# design.net
KiCad netlist of a schematic drawn in Altium Designer
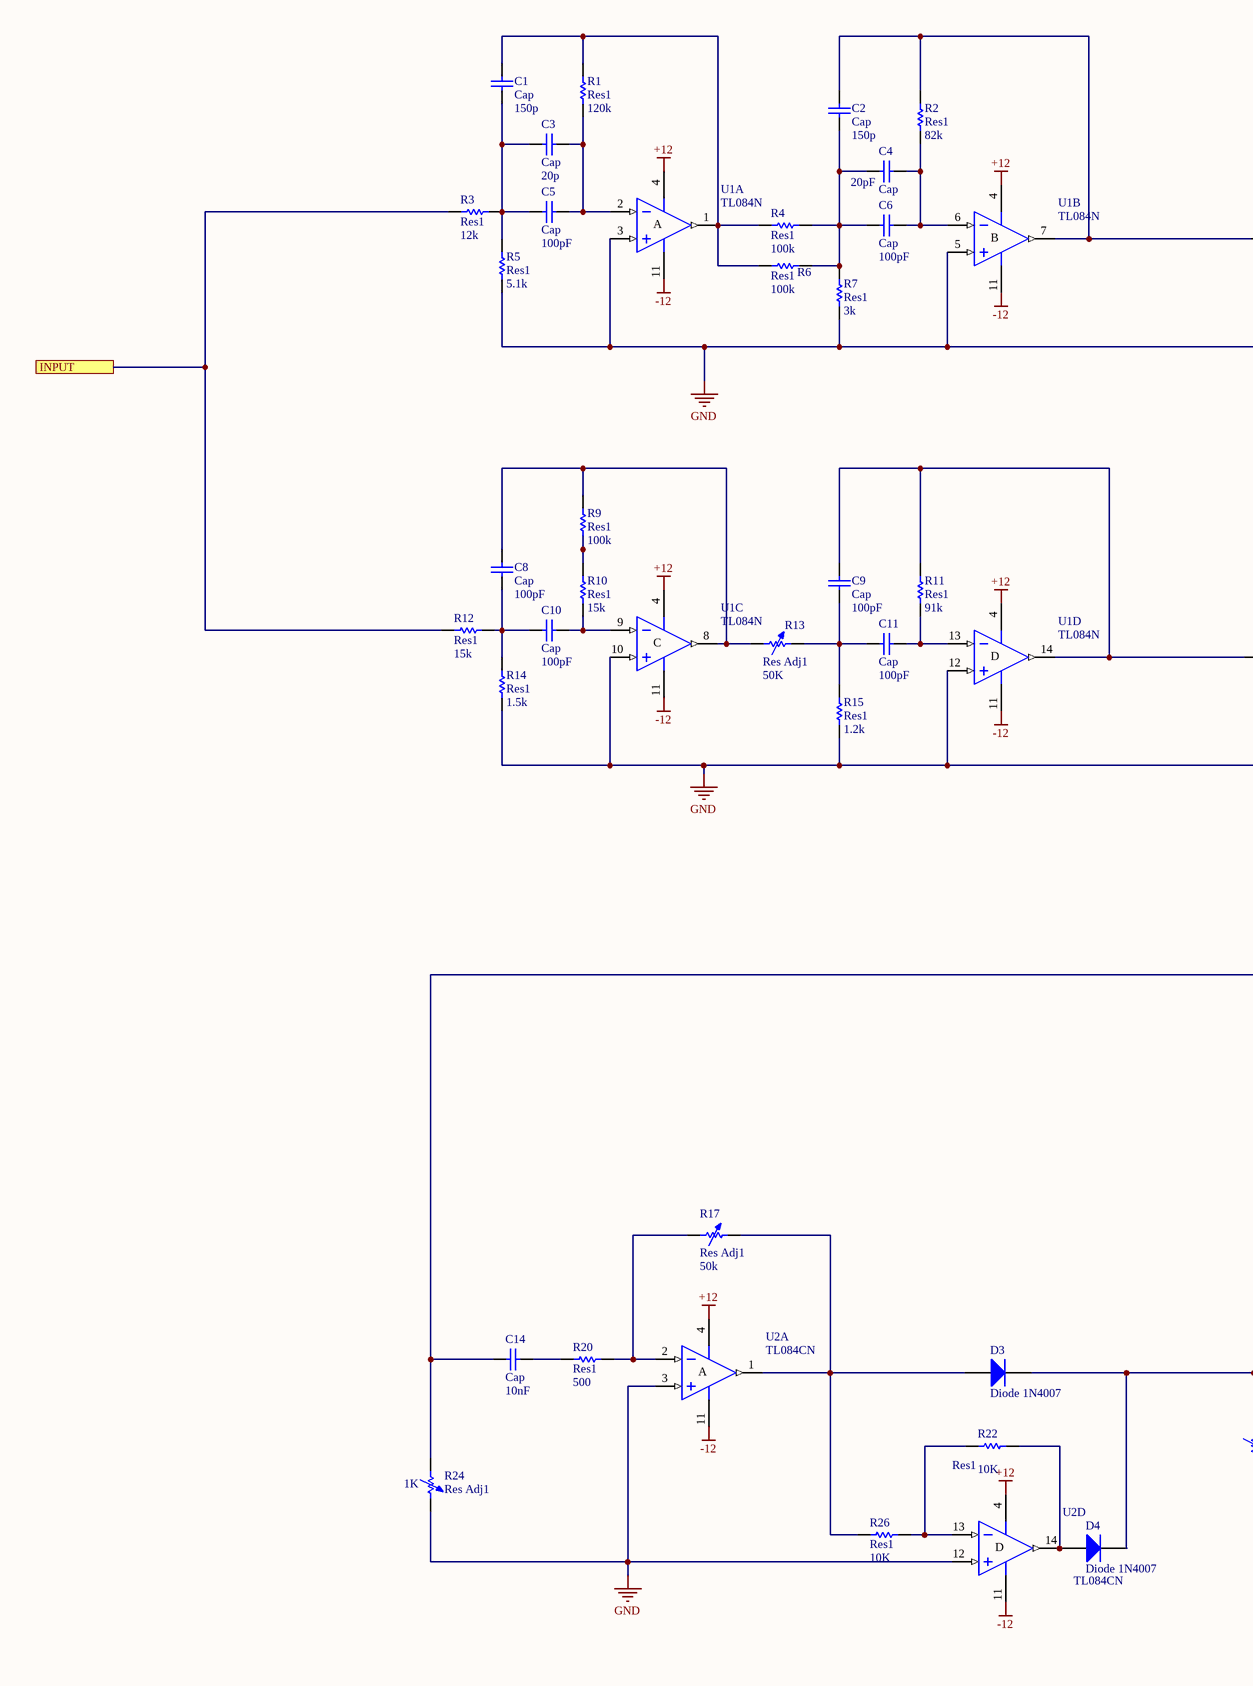
[diagram p0: 解调板原理图.SchDoc, left]
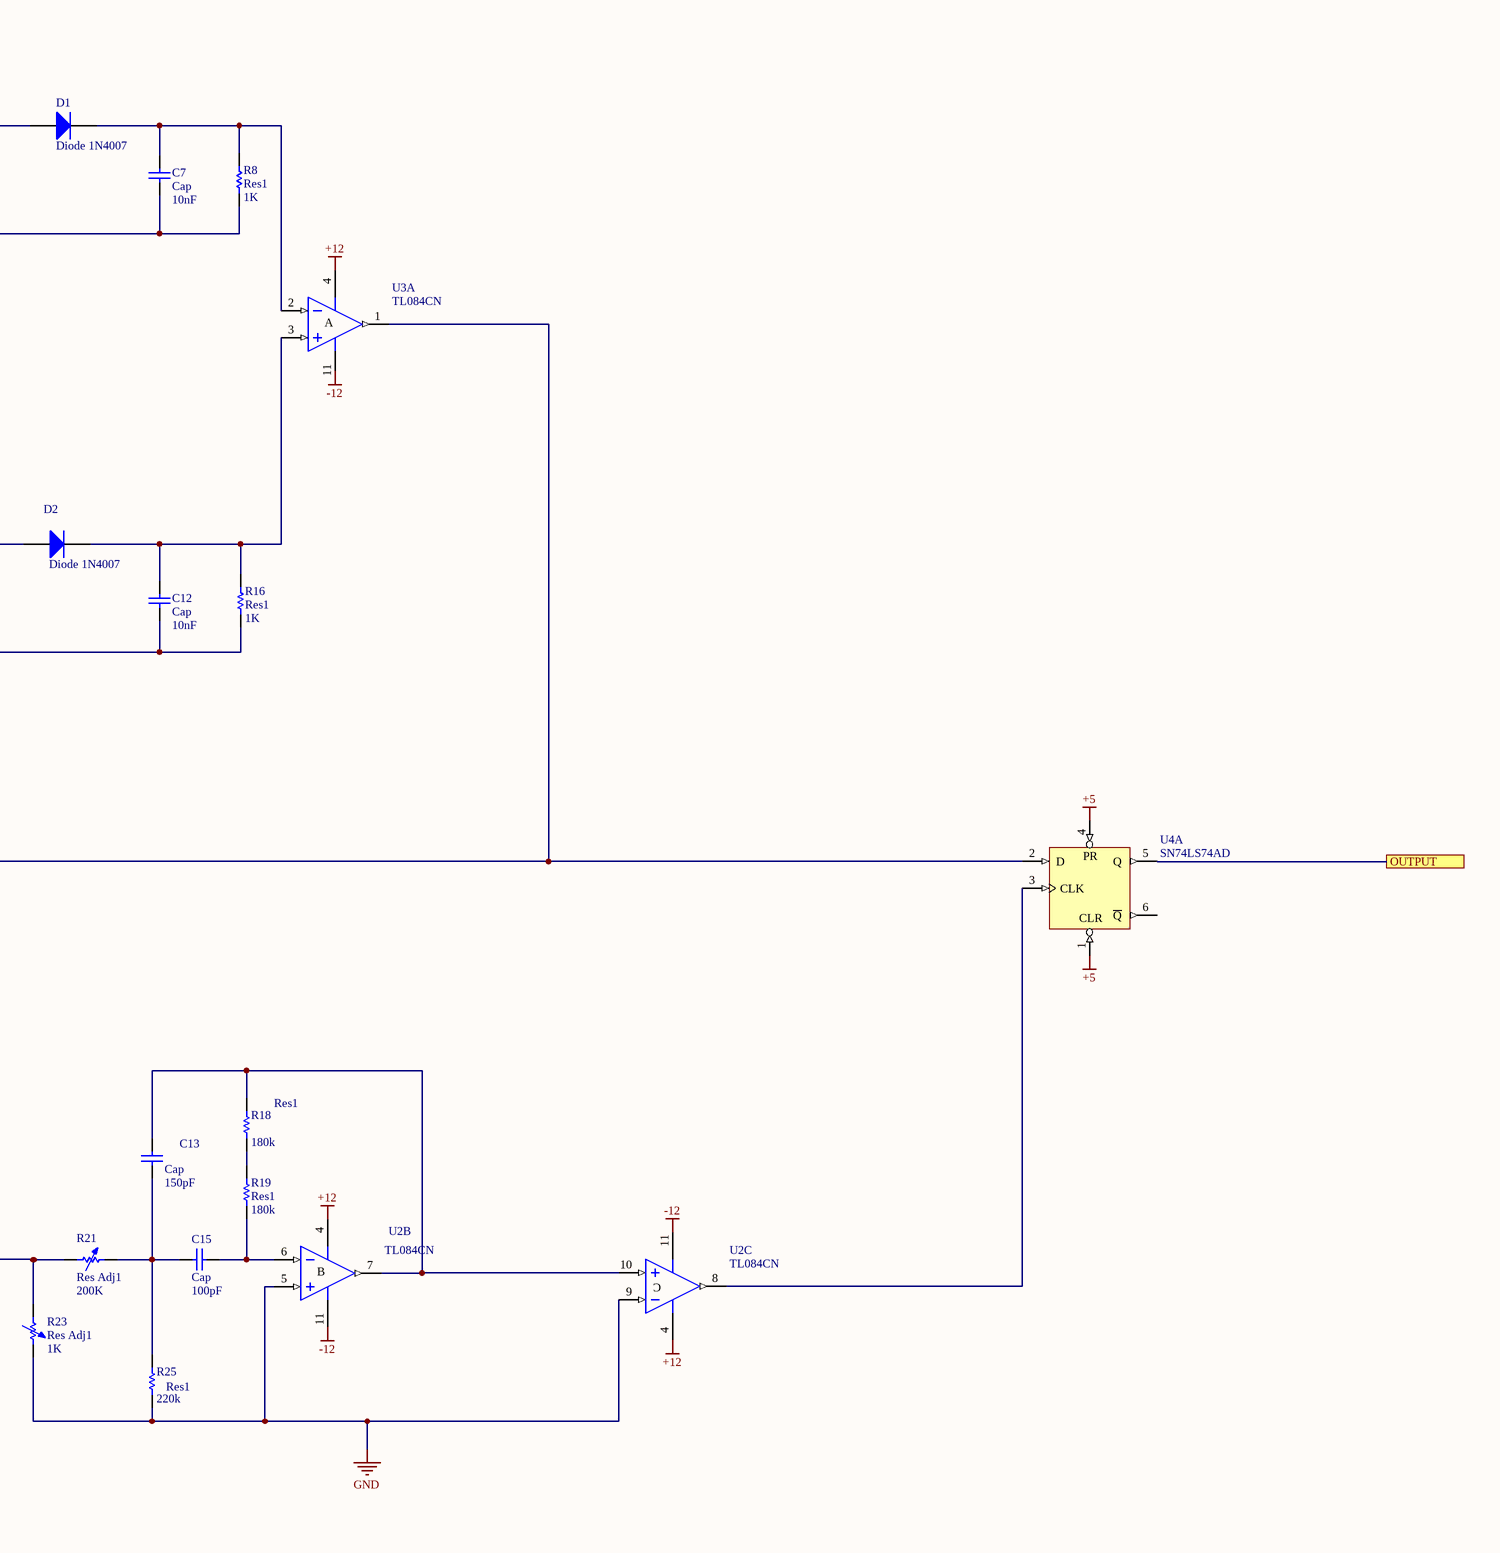
[diagram p1: 解调板原理图.SchDoc, right]

(export (version "E")
  (design (tool "Eeschema 10.0.6"))
  (components
    (comp (ref "C1")
      (value "Cap")
      (footprint "RAD-0.3")
      (description "Capacitor")
      (fields (field (name "ALTIUM_VALUE") "150p") (field (name "PUBLISHER") "Altium Limited"))
      (libsource (lib "Miscellaneous Devices") (part "Cap"))
    )
    (comp (ref "C2")
      (value "Cap")
      (footprint "RAD-0.3")
      (description "Capacitor")
      (fields (field (name "ALTIUM_VALUE") "150p") (field (name "PUBLISHER") "Altium Limited"))
      (libsource (lib "Miscellaneous Devices") (part "Cap"))
    )
    (comp (ref "C3")
      (value "Cap")
      (footprint "RAD-0.3")
      (description "Capacitor")
      (fields (field (name "ALTIUM_VALUE") "20p") (field (name "PUBLISHER") "Altium Limited"))
      (libsource (lib "Miscellaneous Devices") (part "Cap"))
    )
    (comp (ref "C4")
      (value "Cap")
      (footprint "RAD-0.3")
      (description "Capacitor")
      (fields (field (name "ALTIUM_VALUE") "20pF") (field (name "PUBLISHER") "Altium Limited"))
      (libsource (lib "Miscellaneous Devices") (part "Cap"))
    )
    (comp (ref "C5")
      (value "Cap")
      (footprint "RAD-0.3")
      (description "Capacitor")
      (fields (field (name "ALTIUM_VALUE") "100pF") (field (name "PUBLISHER") "Altium Limited"))
      (libsource (lib "Miscellaneous Devices") (part "Cap"))
    )
    (comp (ref "C6")
      (value "Cap")
      (footprint "RAD-0.3")
      (description "Capacitor")
      (fields (field (name "ALTIUM_VALUE") "100pF") (field (name "PUBLISHER") "Altium Limited"))
      (libsource (lib "Miscellaneous Devices") (part "Cap"))
    )
    (comp (ref "C7")
      (value "Cap")
      (footprint "RAD-0.3")
      (description "Capacitor")
      (fields (field (name "ALTIUM_VALUE") "10nF") (field (name "PUBLISHER") "Altium Limited"))
      (libsource (lib "Miscellaneous Devices") (part "Cap"))
    )
    (comp (ref "C8")
      (value "Cap")
      (footprint "RAD-0.3")
      (description "Capacitor")
      (fields (field (name "ALTIUM_VALUE") "100pF") (field (name "PUBLISHER") "Altium Limited"))
      (libsource (lib "Miscellaneous Devices") (part "Cap"))
    )
    (comp (ref "C9")
      (value "Cap")
      (footprint "RAD-0.3")
      (description "Capacitor")
      (fields (field (name "ALTIUM_VALUE") "100pF") (field (name "PUBLISHER") "Altium Limited"))
      (libsource (lib "Miscellaneous Devices") (part "Cap"))
    )
    (comp (ref "C10")
      (value "Cap")
      (footprint "RAD-0.3")
      (description "Capacitor")
      (fields (field (name "ALTIUM_VALUE") "100pF") (field (name "PUBLISHER") "Altium Limited"))
      (libsource (lib "Miscellaneous Devices") (part "Cap"))
    )
    (comp (ref "C11")
      (value "Cap")
      (footprint "RAD-0.3")
      (description "Capacitor")
      (fields (field (name "ALTIUM_VALUE") "100pF") (field (name "PUBLISHER") "Altium Limited"))
      (libsource (lib "Miscellaneous Devices") (part "Cap"))
    )
    (comp (ref "C12")
      (value "Cap")
      (footprint "RAD-0.3")
      (description "Capacitor")
      (fields (field (name "ALTIUM_VALUE") "10nF") (field (name "PUBLISHER") "Altium Limited"))
      (libsource (lib "Miscellaneous Devices") (part "Cap"))
    )
    (comp (ref "C13")
      (value "Cap")
      (footprint "RAD-0.3")
      (description "Capacitor")
      (fields (field (name "ALTIUM_VALUE") "150pF") (field (name "PUBLISHER") "Altium Limited"))
      (libsource (lib "Miscellaneous Devices") (part "Cap"))
    )
    (comp (ref "C14")
      (value "Cap")
      (footprint "RAD-0.3")
      (description "Capacitor")
      (fields (field (name "ALTIUM_VALUE") "10nF") (field (name "PUBLISHER") "Altium Limited"))
      (libsource (lib "Miscellaneous Devices") (part "Cap"))
    )
    (comp (ref "C15")
      (value "Cap")
      (footprint "RAD-0.3")
      (description "Capacitor")
      (fields (field (name "ALTIUM_VALUE") "100pF") (field (name "PUBLISHER") "Altium Limited"))
      (libsource (lib "Miscellaneous Devices") (part "Cap"))
    )
    (comp (ref "D1")
      (value "Diode 1N4007")
      (footprint "DO-41")
      (description "1 Amp General Purpose Rectifier")
      (fields (field (name "PUBLISHER") "Altium Limited"))
      (libsource (lib "Miscellaneous Devices") (part "Diode 1N4001"))
    )
    (comp (ref "D2")
      (value "Diode 1N4007")
      (footprint "DO-41")
      (description "1 Amp General Purpose Rectifier")
      (fields (field (name "PUBLISHER") "Altium Limited"))
      (libsource (lib "Miscellaneous Devices") (part "Diode 1N4001"))
    )
    (comp (ref "D3")
      (value "Diode 1N4007")
      (footprint "DO-41")
      (description "1 Amp General Purpose Rectifier")
      (fields (field (name "PUBLISHER") "Altium Limited"))
      (libsource (lib "Miscellaneous Devices") (part "Diode 1N4001"))
    )
    (comp (ref "D4")
      (value "Diode 1N4007")
      (footprint "DO-41")
      (description "1 Amp General Purpose Rectifier")
      (fields (field (name "PUBLISHER") "Altium Limited"))
      (libsource (lib "Miscellaneous Devices") (part "Diode 1N4001"))
    )
    (comp (ref "R1")
      (value "Res1")
      (footprint "AXIAL-0.3")
      (description "Resistor")
      (fields (field (name "ALTIUM_VALUE") "120k") (field (name "PUBLISHER") "Altium Limited"))
      (libsource (lib "Miscellaneous Devices") (part "Res1"))
    )
    (comp (ref "R2")
      (value "Res1")
      (footprint "AXIAL-0.3")
      (description "Resistor")
      (fields (field (name "ALTIUM_VALUE") "82k") (field (name "PUBLISHER") "Altium Limited"))
      (libsource (lib "Miscellaneous Devices") (part "Res1"))
    )
    (comp (ref "R3")
      (value "Res1")
      (footprint "AXIAL-0.3")
      (description "Resistor")
      (fields (field (name "ALTIUM_VALUE") "12k") (field (name "PUBLISHER") "Altium Limited"))
      (libsource (lib "Miscellaneous Devices") (part "Res1"))
    )
    (comp (ref "R4")
      (value "Res1")
      (footprint "AXIAL-0.3")
      (description "Resistor")
      (fields (field (name "ALTIUM_VALUE") "100k") (field (name "PUBLISHER") "Altium Limited"))
      (libsource (lib "Miscellaneous Devices") (part "Res1"))
    )
    (comp (ref "R5")
      (value "Res1")
      (footprint "AXIAL-0.3")
      (description "Resistor")
      (fields (field (name "ALTIUM_VALUE") "5.1k") (field (name "PUBLISHER") "Altium Limited"))
      (libsource (lib "Miscellaneous Devices") (part "Res1"))
    )
    (comp (ref "R6")
      (value "Res1")
      (footprint "AXIAL-0.3")
      (description "Resistor")
      (fields (field (name "ALTIUM_VALUE") "100k") (field (name "PUBLISHER") "Altium Limited"))
      (libsource (lib "Miscellaneous Devices") (part "Res1"))
    )
    (comp (ref "R7")
      (value "Res1")
      (footprint "AXIAL-0.3")
      (description "Resistor")
      (fields (field (name "ALTIUM_VALUE") "3k") (field (name "PUBLISHER") "Altium Limited"))
      (libsource (lib "Miscellaneous Devices") (part "Res1"))
    )
    (comp (ref "R8")
      (value "Res1")
      (footprint "AXIAL-0.3")
      (description "Resistor")
      (fields (field (name "ALTIUM_VALUE") "1K") (field (name "PUBLISHER") "Altium Limited"))
      (libsource (lib "Miscellaneous Devices") (part "Res1"))
    )
    (comp (ref "R9")
      (value "Res1")
      (footprint "AXIAL-0.3")
      (description "Resistor")
      (fields (field (name "ALTIUM_VALUE") "100k") (field (name "PUBLISHER") "Altium Limited"))
      (libsource (lib "Miscellaneous Devices") (part "Res1"))
    )
    (comp (ref "R10")
      (value "Res1")
      (footprint "AXIAL-0.3")
      (description "Resistor")
      (fields (field (name "ALTIUM_VALUE") "15k") (field (name "PUBLISHER") "Altium Limited"))
      (libsource (lib "Miscellaneous Devices") (part "Res1"))
    )
    (comp (ref "R11")
      (value "Res1")
      (footprint "AXIAL-0.3")
      (description "Resistor")
      (fields (field (name "ALTIUM_VALUE") "91k") (field (name "PUBLISHER") "Altium Limited"))
      (libsource (lib "Miscellaneous Devices") (part "Res1"))
    )
    (comp (ref "R12")
      (value "Res1")
      (footprint "AXIAL-0.3")
      (description "Resistor")
      (fields (field (name "ALTIUM_VALUE") "15k") (field (name "PUBLISHER") "Altium Limited"))
      (libsource (lib "Miscellaneous Devices") (part "Res1"))
    )
    (comp (ref "R13")
      (value "Res Adj1")
      (footprint "AXIAL-0.7")
      (description "Variable Resistor")
      (fields (field (name "ALTIUM_VALUE") "50K") (field (name "PUBLISHER") "Altium Limited"))
      (libsource (lib "Miscellaneous Devices") (part "Res Adj1"))
    )
    (comp (ref "R14")
      (value "Res1")
      (footprint "AXIAL-0.3")
      (description "Resistor")
      (fields (field (name "ALTIUM_VALUE") "1.5k") (field (name "PUBLISHER") "Altium Limited"))
      (libsource (lib "Miscellaneous Devices") (part "Res1"))
    )
    (comp (ref "R15")
      (value "Res1")
      (footprint "AXIAL-0.3")
      (description "Resistor")
      (fields (field (name "ALTIUM_VALUE") "1.2k") (field (name "PUBLISHER") "Altium Limited"))
      (libsource (lib "Miscellaneous Devices") (part "Res1"))
    )
    (comp (ref "R16")
      (value "Res1")
      (footprint "AXIAL-0.3")
      (description "Resistor")
      (fields (field (name "ALTIUM_VALUE") "1K") (field (name "PUBLISHER") "Altium Limited"))
      (libsource (lib "Miscellaneous Devices") (part "Res1"))
    )
    (comp (ref "R17")
      (value "Res Adj1")
      (footprint "AXIAL-0.7")
      (description "Variable Resistor")
      (fields (field (name "ALTIUM_VALUE") "50k") (field (name "PUBLISHER") "Altium Limited"))
      (libsource (lib "Miscellaneous Devices") (part "Res Adj1"))
    )
    (comp (ref "R18")
      (value "Res1")
      (footprint "AXIAL-0.3")
      (description "Resistor")
      (fields (field (name "ALTIUM_VALUE") "180k") (field (name "PUBLISHER") "Altium Limited"))
      (libsource (lib "Miscellaneous Devices") (part "Res1"))
    )
    (comp (ref "R19")
      (value "Res1")
      (footprint "AXIAL-0.3")
      (description "Resistor")
      (fields (field (name "ALTIUM_VALUE") "180k") (field (name "PUBLISHER") "Altium Limited"))
      (libsource (lib "Miscellaneous Devices") (part "Res1"))
    )
    (comp (ref "R20")
      (value "Res1")
      (footprint "AXIAL-0.3")
      (description "Resistor")
      (fields (field (name "ALTIUM_VALUE") "500") (field (name "PUBLISHER") "Altium Limited"))
      (libsource (lib "Miscellaneous Devices") (part "Res1"))
    )
    (comp (ref "R21")
      (value "Res Adj1")
      (footprint "AXIAL-0.7")
      (description "Variable Resistor")
      (fields (field (name "ALTIUM_VALUE") "200K") (field (name "PUBLISHER") "Altium Limited"))
      (libsource (lib "Miscellaneous Devices") (part "Res Adj1"))
    )
    (comp (ref "R22")
      (value "Res1")
      (footprint "AXIAL-0.3")
      (description "Resistor")
      (fields (field (name "ALTIUM_VALUE") "10K") (field (name "PUBLISHER") "Altium Limited"))
      (libsource (lib "Miscellaneous Devices") (part "Res1"))
    )
    (comp (ref "R23")
      (value "Res Adj1")
      (footprint "AXIAL-0.7")
      (description "Variable Resistor")
      (fields (field (name "ALTIUM_VALUE") "1K") (field (name "PUBLISHER") "Altium Limited"))
      (libsource (lib "Miscellaneous Devices") (part "Res Adj1"))
    )
    (comp (ref "R24")
      (value "Res Adj1")
      (footprint "AXIAL-0.7")
      (description "Variable Resistor")
      (fields (field (name "ALTIUM_VALUE") "1K") (field (name "PUBLISHER") "Altium Limited"))
      (libsource (lib "Miscellaneous Devices") (part "Res Adj1"))
    )
    (comp (ref "R25")
      (value "Res1")
      (footprint "AXIAL-0.3")
      (description "Resistor")
      (fields (field (name "ALTIUM_VALUE") "220k") (field (name "PUBLISHER") "Altium Limited"))
      (libsource (lib "Miscellaneous Devices") (part "Res1"))
    )
    (comp (ref "R26")
      (value "Res1")
      (footprint "AXIAL-0.3")
      (description "Resistor")
      (fields (field (name "ALTIUM_VALUE") "10K") (field (name "PUBLISHER") "Altium Limited"))
      (libsource (lib "Miscellaneous Devices") (part "Res1"))
    )
    (comp (ref "U1")
      (value "TL084N")
      (footprint "N014")
      (description "JFET-Input Operational Amplifier")
      (fields (field (name "PUBLISHER") "Altium Limited"))
      (libsource (lib "TI Operational Amplifier") (part "TL084N"))
    )
    (comp (ref "U2")
      (value "TL084CN")
      (footprint "DIP14")
      (description "General-Purpose J-FET Quad Operational Amplifier")
      (fields (field (name "PUBLISHER") "Altium Limited"))
      (libsource (lib "ST Operational Amplifier") (part "TL084CN"))
    )
    (comp (ref "U3")
      (value "TL084CN")
      (footprint "DIP14")
      (description "General-Purpose J-FET Quad Operational Amplifier")
      (fields (field (name "PUBLISHER") "Altium Limited"))
      (libsource (lib "ST Operational Amplifier") (part "TL084CN"))
    )
    (comp (ref "U4")
      (value "SN74LS74AD")
      (footprint "D014_L")
      (description "Dual D-Type Positive-Edge-Triggered Flip-Flop with Preset and Clear")
      (fields (field (name "PUBLISHER") "Altium Limited"))
      (libsource (lib "TI Logic Flip-Flop") (part "SN74LS74AD"))
    )
  )
  (nets
    (net (code "1") (name "+5") (class "Default")
      (node (ref "U4") (pin "1") (pinfunction "CLR_1") (pintype "input"))
      (node (ref "U4") (pin "4") (pinfunction "PR_4") (pintype "input"))
    )
    (net (code "2") (name "+12") (class "Default")
      (node (ref "U1") (pin "4") (pinfunction "V+_4") (pintype "power_in"))
      (node (ref "U2") (pin "4") (pinfunction "V+_4") (pintype "power_in"))
      (node (ref "U3") (pin "4") (pinfunction "V+_4") (pintype "power_in"))
    )
    (net (code "3") (name "-12") (class "Default")
      (node (ref "U1") (pin "11") (pinfunction "V-_11") (pintype "power_in"))
      (node (ref "U2") (pin "11") (pinfunction "V-_11") (pintype "power_in"))
    )
    (net (code "4") (name "/INPUT") (class "Default")
      (node (ref "R12") (pin "1") (pinfunction "1_1") (pintype "passive"))
      (node (ref "R3") (pin "1") (pinfunction "1_1") (pintype "passive"))
    )
    (net (code "5") (name "/OUTPUT") (class "Default")
      (node (ref "U4") (pin "5") (pinfunction "Q_5") (pintype "output"))
    )
    (net (code "6") (name "GND") (class "Default")
      (node (ref "C12") (pin "1") (pinfunction "1_1") (pintype "passive"))
      (node (ref "C7") (pin "1") (pinfunction "1_1") (pintype "passive"))
      (node (ref "R14") (pin "1") (pinfunction "1_1") (pintype "passive"))
      (node (ref "R15") (pin "1") (pinfunction "1_1") (pintype "passive"))
      (node (ref "R16") (pin "1") (pinfunction "1_1") (pintype "passive"))
      (node (ref "R23") (pin "2") (pinfunction "2_2") (pintype "passive"))
      (node (ref "R24") (pin "2") (pinfunction "2_2") (pintype "passive"))
      (node (ref "R25") (pin "1") (pinfunction "1_1") (pintype "passive"))
      (node (ref "R5") (pin "1") (pinfunction "1_1") (pintype "passive"))
      (node (ref "R7") (pin "1") (pinfunction "1_1") (pintype "passive"))
      (node (ref "R8") (pin "1") (pinfunction "1_1") (pintype "passive"))
      (node (ref "U1") (pin "10") (pinfunction "IN+_10") (pintype "input"))
      (node (ref "U1") (pin "12") (pinfunction "IN+_12") (pintype "input"))
      (node (ref "U1") (pin "3") (pinfunction "IN+_3") (pintype "input"))
      (node (ref "U1") (pin "5") (pinfunction "IN+_5") (pintype "input"))
      (node (ref "U2") (pin "12") (pinfunction "IN+_12") (pintype "input"))
      (node (ref "U2") (pin "3") (pinfunction "IN+_3") (pintype "input"))
      (node (ref "U2") (pin "5") (pinfunction "IN+_5") (pintype "input"))
      (node (ref "U2") (pin "9") (pinfunction "IN-_9") (pintype "input"))
      (node (ref "U4") (pin "7") (pinfunction "GND_7") (pintype "power_in"))
    )
    (net (code "7") (name "Net-(C1-Pad1)") (class "Default")
      (node (ref "C1") (pin "1") (pinfunction "1_1") (pintype "passive"))
      (node (ref "C3") (pin "1") (pinfunction "1_1") (pintype "passive"))
      (node (ref "C5") (pin "1") (pinfunction "1_1") (pintype "passive"))
      (node (ref "R3") (pin "2") (pinfunction "2_2") (pintype "passive"))
      (node (ref "R5") (pin "2") (pinfunction "2_2") (pintype "passive"))
    )
    (net (code "8") (name "Net-(C2-Pad1)") (class "Default")
      (node (ref "C2") (pin "1") (pinfunction "1_1") (pintype "passive"))
      (node (ref "C4") (pin "1") (pinfunction "1_1") (pintype "passive"))
      (node (ref "C6") (pin "1") (pinfunction "1_1") (pintype "passive"))
      (node (ref "R4") (pin "2") (pinfunction "2_2") (pintype "passive"))
      (node (ref "R6") (pin "2") (pinfunction "2_2") (pintype "passive"))
      (node (ref "R7") (pin "2") (pinfunction "2_2") (pintype "passive"))
    )
    (net (code "9") (name "Net-(C10-Pad1)") (class "Default")
      (node (ref "C10") (pin "1") (pinfunction "1_1") (pintype "passive"))
      (node (ref "C8") (pin "1") (pinfunction "1_1") (pintype "passive"))
      (node (ref "R12") (pin "2") (pinfunction "2_2") (pintype "passive"))
      (node (ref "R14") (pin "2") (pinfunction "2_2") (pintype "passive"))
    )
    (net (code "10") (name "Net-(C11-Pad1)") (class "Default")
      (node (ref "C11") (pin "1") (pinfunction "1_1") (pintype "passive"))
      (node (ref "C9") (pin "1") (pinfunction "1_1") (pintype "passive"))
      (node (ref "R13") (pin "2") (pinfunction "2_2") (pintype "passive"))
      (node (ref "R15") (pin "2") (pinfunction "2_2") (pintype "passive"))
    )
    (net (code "11") (name "Net-(C13-Pad1)") (class "Default")
      (node (ref "C13") (pin "1") (pinfunction "1_1") (pintype "passive"))
      (node (ref "C15") (pin "1") (pinfunction "1_1") (pintype "passive"))
      (node (ref "R21") (pin "2") (pinfunction "2_2") (pintype "passive"))
      (node (ref "R25") (pin "2") (pinfunction "2_2") (pintype "passive"))
    )
    (net (code "12") (name "Net-(C14-Pad2)") (class "Default")
      (node (ref "C14") (pin "2") (pinfunction "2_2") (pintype "passive"))
      (node (ref "R20") (pin "1") (pinfunction "1_1") (pintype "passive"))
    )
    (net (code "13") (name "Net-(D1-A)") (class "Default")
      (node (ref "C2") (pin "2") (pinfunction "2_2") (pintype "passive"))
      (node (ref "D1") (pin "1") (pinfunction "A_1") (pintype "passive"))
      (node (ref "R2") (pin "2") (pinfunction "2_2") (pintype "passive"))
      (node (ref "U1") (pin "7") (pinfunction "OUT_7") (pintype "output"))
    )
    (net (code "14") (name "Net-(D1-K)") (class "Default")
      (node (ref "C7") (pin "2") (pinfunction "2_2") (pintype "passive"))
      (node (ref "D1") (pin "2") (pinfunction "K_2") (pintype "passive"))
      (node (ref "R8") (pin "2") (pinfunction "2_2") (pintype "passive"))
      (node (ref "U3") (pin "2") (pinfunction "IN-_2") (pintype "input"))
    )
    (net (code "15") (name "Net-(D2-A)") (class "Default")
      (node (ref "C9") (pin "2") (pinfunction "2_2") (pintype "passive"))
      (node (ref "D2") (pin "1") (pinfunction "A_1") (pintype "passive"))
      (node (ref "R11") (pin "2") (pinfunction "2_2") (pintype "passive"))
      (node (ref "U1") (pin "14") (pinfunction "OUT_14") (pintype "output"))
    )
    (net (code "16") (name "Net-(D2-K)") (class "Default")
      (node (ref "C12") (pin "2") (pinfunction "2_2") (pintype "passive"))
      (node (ref "D2") (pin "2") (pinfunction "K_2") (pintype "passive"))
      (node (ref "R16") (pin "2") (pinfunction "2_2") (pintype "passive"))
      (node (ref "U3") (pin "3") (pinfunction "IN+_3") (pintype "input"))
    )
    (net (code "17") (name "Net-(D3-A)") (class "Default")
      (node (ref "D3") (pin "1") (pinfunction "A_1") (pintype "passive"))
      (node (ref "R17") (pin "2") (pinfunction "2_2") (pintype "passive"))
      (node (ref "R26") (pin "1") (pinfunction "1_1") (pintype "passive"))
      (node (ref "U2") (pin "1") (pinfunction "OUT_1") (pintype "output"))
    )
    (net (code "18") (name "Net-(D3-K)") (class "Default")
      (node (ref "D3") (pin "2") (pinfunction "K_2") (pintype "passive"))
      (node (ref "D4") (pin "2") (pinfunction "K_2") (pintype "passive"))
      (node (ref "R21") (pin "1") (pinfunction "1_1") (pintype "passive"))
      (node (ref "R23") (pin "1") (pinfunction "1_1") (pintype "passive"))
    )
    (net (code "19") (name "Net-(D4-A)") (class "Default")
      (node (ref "D4") (pin "1") (pinfunction "A_1") (pintype "passive"))
      (node (ref "R22") (pin "2") (pinfunction "2_2") (pintype "passive"))
      (node (ref "U2") (pin "14") (pinfunction "OUT_14") (pintype "output"))
    )
    (net (code "20") (name "Net-(R10-Pad2)") (class "Default")
      (node (ref "R10") (pin "2") (pinfunction "2_2") (pintype "passive"))
      (node (ref "R9") (pin "1") (pinfunction "1_1") (pintype "passive"))
    )
    (net (code "21") (name "Net-(R18-Pad1)") (class "Default")
      (node (ref "R18") (pin "1") (pinfunction "1_1") (pintype "passive"))
      (node (ref "R19") (pin "2") (pinfunction "2_2") (pintype "passive"))
    )
    (net (code "22") (name "Net-(U1A-IN-)") (class "Default")
      (node (ref "C3") (pin "2") (pinfunction "2_2") (pintype "passive"))
      (node (ref "C5") (pin "2") (pinfunction "2_2") (pintype "passive"))
      (node (ref "R1") (pin "1") (pinfunction "1_1") (pintype "passive"))
      (node (ref "U1") (pin "2") (pinfunction "IN-_2") (pintype "input"))
    )
    (net (code "23") (name "Net-(U1A-OUT)") (class "Default")
      (node (ref "C1") (pin "2") (pinfunction "2_2") (pintype "passive"))
      (node (ref "R1") (pin "2") (pinfunction "2_2") (pintype "passive"))
      (node (ref "R4") (pin "1") (pinfunction "1_1") (pintype "passive"))
      (node (ref "R6") (pin "1") (pinfunction "1_1") (pintype "passive"))
      (node (ref "U1") (pin "1") (pinfunction "OUT_1") (pintype "output"))
    )
    (net (code "24") (name "Net-(U1B-IN-)") (class "Default")
      (node (ref "C4") (pin "2") (pinfunction "2_2") (pintype "passive"))
      (node (ref "C6") (pin "2") (pinfunction "2_2") (pintype "passive"))
      (node (ref "R2") (pin "1") (pinfunction "1_1") (pintype "passive"))
      (node (ref "U1") (pin "6") (pinfunction "IN-_6") (pintype "input"))
    )
    (net (code "25") (name "Net-(U1C-IN-)") (class "Default")
      (node (ref "C10") (pin "2") (pinfunction "2_2") (pintype "passive"))
      (node (ref "R10") (pin "1") (pinfunction "1_1") (pintype "passive"))
      (node (ref "U1") (pin "9") (pinfunction "IN-_9") (pintype "input"))
    )
    (net (code "26") (name "Net-(U1C-OUT)") (class "Default")
      (node (ref "C8") (pin "2") (pinfunction "2_2") (pintype "passive"))
      (node (ref "R13") (pin "1") (pinfunction "1_1") (pintype "passive"))
      (node (ref "R9") (pin "2") (pinfunction "2_2") (pintype "passive"))
      (node (ref "U1") (pin "8") (pinfunction "OUT_8") (pintype "output"))
    )
    (net (code "27") (name "Net-(U1D-IN-)") (class "Default")
      (node (ref "C11") (pin "2") (pinfunction "2_2") (pintype "passive"))
      (node (ref "R11") (pin "1") (pinfunction "1_1") (pintype "passive"))
      (node (ref "U1") (pin "13") (pinfunction "IN-_13") (pintype "input"))
    )
    (net (code "28") (name "Net-(U2A-IN-)") (class "Default")
      (node (ref "R17") (pin "1") (pinfunction "1_1") (pintype "passive"))
      (node (ref "R20") (pin "2") (pinfunction "2_2") (pintype "passive"))
      (node (ref "U2") (pin "2") (pinfunction "IN-_2") (pintype "input"))
    )
    (net (code "29") (name "Net-(U2B-IN-)") (class "Default")
      (node (ref "C15") (pin "2") (pinfunction "2_2") (pintype "passive"))
      (node (ref "R19") (pin "1") (pinfunction "1_1") (pintype "passive"))
      (node (ref "U2") (pin "6") (pinfunction "IN-_6") (pintype "input"))
    )
    (net (code "30") (name "Net-(U2B-OUT)") (class "Default")
      (node (ref "C13") (pin "2") (pinfunction "2_2") (pintype "passive"))
      (node (ref "R18") (pin "2") (pinfunction "2_2") (pintype "passive"))
      (node (ref "U2") (pin "10") (pinfunction "IN+_10") (pintype "input"))
      (node (ref "U2") (pin "7") (pinfunction "OUT_7") (pintype "output"))
    )
    (net (code "31") (name "Net-(U2C-OUT)") (class "Default")
      (node (ref "U2") (pin "8") (pinfunction "OUT_8") (pintype "output"))
      (node (ref "U4") (pin "3") (pinfunction "CLK_3") (pintype "input"))
    )
    (net (code "32") (name "Net-(U2D-IN-)") (class "Default")
      (node (ref "R22") (pin "1") (pinfunction "1_1") (pintype "passive"))
      (node (ref "R26") (pin "2") (pinfunction "2_2") (pintype "passive"))
      (node (ref "U2") (pin "13") (pinfunction "IN-_13") (pintype "input"))
    )
    (net (code "33") (name "Net-(U3A-OUT)") (class "Default")
      (node (ref "C14") (pin "1") (pinfunction "1_1") (pintype "passive"))
      (node (ref "R24") (pin "1") (pinfunction "1_1") (pintype "passive"))
      (node (ref "U3") (pin "1") (pinfunction "OUT_1") (pintype "output"))
      (node (ref "U4") (pin "2") (pinfunction "D_2") (pintype "input"))
    )
    (net (code "34") (name "VCC") (class "Default")
      (node (ref "U4") (pin "14") (pinfunction "VCC_14") (pintype "power_in"))
    )
    (net (code "35") (name "unconnected-(U3A-V--Pad11)") (class "Default")
      (node (ref "U3") (pin "11") (pinfunction "V-_11") (pintype "power_in"))
    )
    (net (code "36") (name "unconnected-(U4A-~{Q}-Pad6)") (class "Default")
      (node (ref "U4") (pin "6") (pinfunction "~{Q}_6") (pintype "output"))
    )
  )
)
